# MINIOLED.net
KiCad netlist of a schematic drawn in Altium Designer
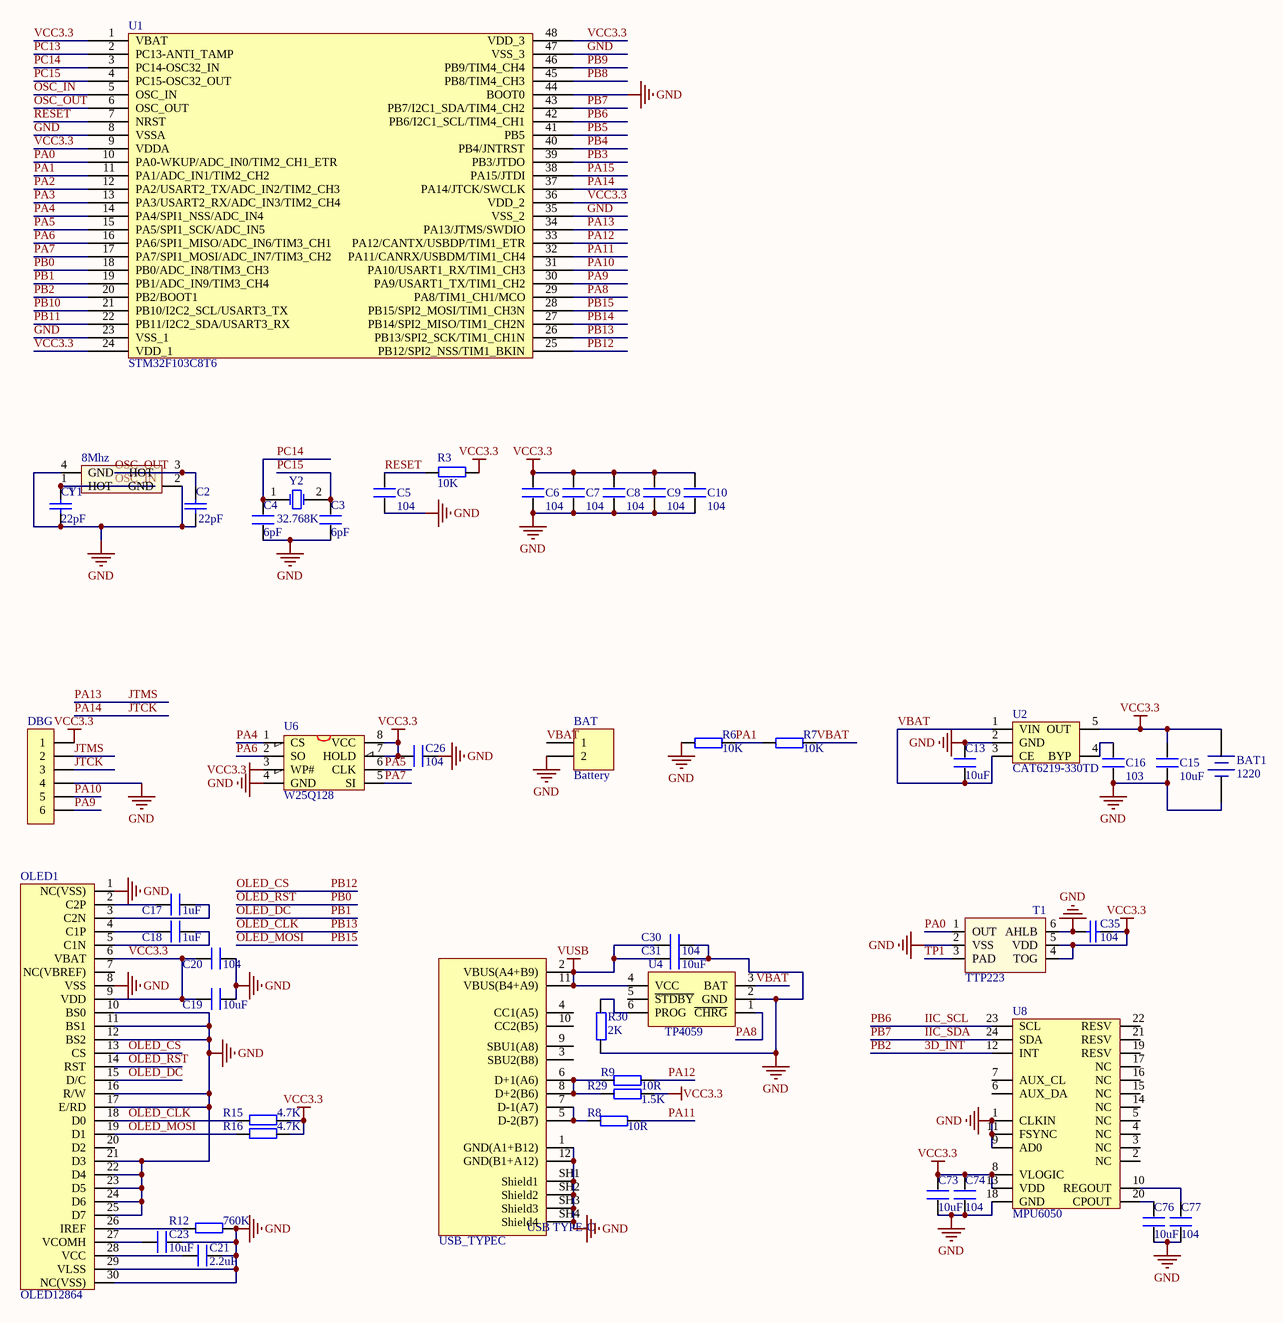
[diagram p0: MINIOLED.SchDoc]

(export (version "E")
  (design (tool "Eeschema 10.0.6"))
  (components
    (comp (ref "BAT")
      (value "Battery")
      (footprint "HDR1X2")
      (description "Header, 2-Pin")
      (fields (field (name "PUBLISHER") "Altium Limited"))
      (libsource (lib "MiniFly ") (part "Header 2"))
    )
    (comp (ref "BAT1")
      (value "1220")
      (footprint "CR1220_B")
      (description "微型电池")
      (fields (field (name "版权归属") "源创客"))
      (libsource (lib "IMX6UL_ALPHA(底板)_V2.0") (part "CR-3V"))
    )
    (comp (ref "C1") (value "22pF") (footprint "C 0402_L") (libsource (lib "L476") (part "CAP")))
    (comp (ref "C2") (value "22pF") (footprint "C 0402_L") (libsource (lib "L476") (part "CAP")))
    (comp (ref "C3")
      (value "6pF")
      (footprint "C 0402_L")
      (libsource (lib "WarShip V3 STM32103封装库") (part "C"))
    )
    (comp (ref "C4")
      (value "6pF")
      (footprint "C 0402_L")
      (libsource (lib "WarShip V3 STM32103封装库") (part "C"))
    )
    (comp (ref "C5")
      (value "104")
      (footprint "C 0402_L")
      (libsource (lib "WarShip V3 STM32103封装库") (part "C"))
    )
    (comp (ref "C6")
      (value "104")
      (footprint "C 0402_L")
      (libsource (lib "WarShip V3 STM32103封装库") (part "C"))
    )
    (comp (ref "C7")
      (value "104")
      (footprint "C 0402_L")
      (libsource (lib "WarShip V3 STM32103封装库") (part "C"))
    )
    (comp (ref "C8")
      (value "104")
      (footprint "C 0402_L")
      (libsource (lib "WarShip V3 STM32103封装库") (part "C"))
    )
    (comp (ref "C9")
      (value "104")
      (footprint "C 0402_L")
      (libsource (lib "WarShip V3 STM32103封装库") (part "C"))
    )
    (comp (ref "C10")
      (value "104")
      (footprint "C 0402_L")
      (libsource (lib "WarShip V3 STM32103封装库") (part "C"))
    )
    (comp (ref "C13")
      (value "10uF")
      (footprint "C 0402_L")
      (libsource (lib "WarShip V3 STM32103封装库") (part "C"))
    )
    (comp (ref "C15")
      (value "10uF")
      (footprint "C 0402_L")
      (libsource (lib "WarShip V3 STM32103封装库") (part "C"))
    )
    (comp (ref "C16")
      (value "103")
      (footprint "C 0402_L")
      (libsource (lib "WarShip V3 STM32103封装库") (part "C"))
    )
    (comp (ref "C17")
      (value "1uF")
      (footprint "C 0402_L")
      (libsource (lib "WarShip V3 STM32103封装库") (part "C"))
    )
    (comp (ref "C18")
      (value "1uF")
      (footprint "C 0402_L")
      (libsource (lib "WarShip V3 STM32103封装库") (part "C"))
    )
    (comp (ref "C19")
      (value "10uF")
      (footprint "C 0402_L")
      (libsource (lib "WarShip V3 STM32103封装库") (part "C"))
    )
    (comp (ref "C20")
      (value "104")
      (footprint "C 0402_L")
      (libsource (lib "WarShip V3 STM32103封装库") (part "C"))
    )
    (comp (ref "C21")
      (value "2.2uF")
      (footprint "C 0402_L")
      (libsource (lib "WarShip V3 STM32103封装库") (part "C"))
    )
    (comp (ref "C23")
      (value "10uF")
      (footprint "C 0402_L")
      (libsource (lib "WarShip V3 STM32103封装库") (part "C"))
    )
    (comp (ref "C26")
      (value "104")
      (footprint "C 0603_L")
      (libsource (lib "WarShip V3 STM32103封装库") (part "C"))
    )
    (comp (ref "C30")
      (value "104")
      (footprint "C 0402_L")
      (libsource (lib "WarShip V3 STM32103封装库") (part "C"))
    )
    (comp (ref "C31")
      (value "10uF")
      (footprint "C 0402_L")
      (libsource (lib "WarShip V3 STM32103封装库") (part "C"))
    )
    (comp (ref "C35")
      (value "104")
      (footprint "C 0402_L")
      (libsource (lib "Pandora_STM32L4_Board_V2.4") (part "C-0603-SMD"))
    )
    (comp (ref "C73") (value "10uF") (footprint "C 0402_L") (libsource (lib "MYCOMLIB") (part "C")))
    (comp (ref "C74") (value "104") (footprint "C 0402_L") (libsource (lib "MYCOMLIB") (part "C")))
    (comp (ref "C76") (value "10uF") (footprint "C 0402_L") (libsource (lib "MYCOMLIB") (part "C")))
    (comp (ref "C77") (value "104") (footprint "C 0402_L") (libsource (lib "MYCOMLIB") (part "C")))
    (comp (ref "DBG")
      (value "GPS&COMPASS")
      (footprint "SH1.0 S-W-6P")
      (description "6P接插件")
      (fields (field (name "版权归属") "源创客"))
      (libsource (lib "ATKF405 V1.1") (part "Header 6"))
    )
    (comp (ref "OLED1")
      (value "OLED12864")
      (footprint "OLED1.3")
      (libsource (lib "OLED模块封装库") (part "OLED12864"))
    )
    (comp (ref "R3")
      (value "10K")
      (footprint "R 0402_L")
      (libsource (lib "WarShip V3 STM32103封装库") (part "R"))
    )
    (comp (ref "R6")
      (value "10K")
      (footprint "R 0402_L")
      (libsource (lib "WarShip V3 STM32103封装库") (part "R"))
    )
    (comp (ref "R7")
      (value "10K")
      (footprint "R 0402_L")
      (libsource (lib "WarShip V3 STM32103封装库") (part "R"))
    )
    (comp (ref "R8")
      (value "10R")
      (footprint "R 0402_L")
      (libsource (lib "WarShip V3 STM32103封装库") (part "R"))
    )
    (comp (ref "R9")
      (value "10R")
      (footprint "R 0402_L")
      (libsource (lib "WarShip V3 STM32103封装库") (part "R"))
    )
    (comp (ref "R12")
      (value "760K")
      (footprint "R 0402_L")
      (libsource (lib "WarShip V3 STM32103封装库") (part "R"))
    )
    (comp (ref "R15")
      (value "4.7K")
      (footprint "R 0402_L")
      (libsource (lib "WarShip V3 STM32103封装库") (part "R"))
    )
    (comp (ref "R16")
      (value "4.7K")
      (footprint "R 0402_L")
      (libsource (lib "WarShip V3 STM32103封装库") (part "R"))
    )
    (comp (ref "R29")
      (value "1.5K")
      (footprint "R 0402_L")
      (libsource (lib "WarShip V3 STM32103封装库") (part "R"))
    )
    (comp (ref "R30")
      (value "2K")
      (footprint "R 0402_L")
      (libsource (lib "WarShip V3 STM32103封装库") (part "R"))
    )
    (comp (ref "T1")
      (value "TTP223")
      (footprint "SOT23-6L")
      (libsource (lib "nrf52832model") (part "TTP223"))
    )
    (comp (ref "U1")
      (value "STM32F103C8T6")
      (footprint "LQFP48 7X7_L")
      (libsource (lib "Pandora_STM32L4_Board_V2.4") (part "U-STM32F103C8T6"))
    )
    (comp (ref "U2")
      (value "CAT6219-330TD")
      (footprint "SOT-23-5")
      (description "3.3V 500mA LDO")
      (libsource (lib "STM32H743核心板封装库") (part "CAT6219-330TD"))
    )
    (comp (ref "U4")
      (value "TP4059")
      (footprint "SOT23-6L")
      (libsource (lib "ATK-2014-09-12") (part "TP4059"))
    )
    (comp (ref "U6")
      (value "W25Q128")
      (footprint "SOP8W_L")
      (description "W25X16;SST25VF016;MX25L1605")
      (libsource (lib "WarShip V3 STM32103封装库") (part "W25X16"))
    )
    (comp (ref "U8")
      (value "MPU6050")
      (footprint "QFN24 4x4_N")
      (description "9轴运动处理传感器")
      (libsource (lib "ALIENTEK_COMPONENT") (part "MPU6050"))
    )
    (comp (ref "USB_TYPEC")
      (value "USB TypeC")
      (footprint "USB Type-C")
      (description "12P TypeC 母座")
      (libsource (lib "ESP32_Weather") (part "USB Type-C"))
    )
    (comp (ref "Y1")
      (value "8Mhz")
      (footprint "XTAL-3225")
      (description "3225贴片无源晶振")
      (libsource (lib "ALIENTEK_COMPONENT") (part "XTAL_3225"))
    )
    (comp (ref "Y2")
      (value "32.768K")
      (footprint "OSC 3215-2P")
      (description "Crystal Oscillator")
      (fields (field (name "PUBLISHER") "Altium Limited"))
      (libsource (lib "WarShip V3 STM32103封装库") (part "XTAL"))
    )
  )
  (nets
    (net (code "1") (name "/3D_INT") (class "Default")
      (node (ref "U1") (pin "20") (pinfunction "PB2/BOOT1_20") (pintype "passive"))
      (node (ref "U8") (pin "12") (pinfunction "INT_12") (pintype "passive"))
    )
    (net (code "2") (name "/IIC_SCL") (class "Default")
      (node (ref "U1") (pin "42") (pinfunction "PB6/I2C1_SCL/TIM4_CH1_42") (pintype "passive"))
      (node (ref "U8") (pin "23") (pinfunction "SCL_23") (pintype "passive"))
    )
    (net (code "3") (name "/IIC_SDA") (class "Default")
      (node (ref "U1") (pin "43") (pinfunction "PB7/I2C1_SDA/TIM4_CH2_43") (pintype "passive"))
      (node (ref "U8") (pin "24") (pinfunction "SDA_24") (pintype "passive"))
    )
    (net (code "4") (name "/JTCK") (class "Default")
      (node (ref "DBG") (pin "3") (pinfunction "3_3") (pintype "passive"))
      (node (ref "U1") (pin "37") (pinfunction "PA14/JTCK/SWCLK_37") (pintype "passive"))
    )
    (net (code "5") (name "/JTMS") (class "Default")
      (node (ref "DBG") (pin "2") (pinfunction "2_2") (pintype "passive"))
      (node (ref "U1") (pin "34") (pinfunction "PA13/JTMS/SWDIO_34") (pintype "passive"))
    )
    (net (code "6") (name "/OLED_CLK") (class "Default")
      (node (ref "OLED1") (pin "18") (pinfunction "D0_18") (pintype "passive"))
      (node (ref "R15") (pin "2") (pintype "passive"))
      (node (ref "U1") (pin "26") (pinfunction "PB13/SPI2_SCK/TIM1_CH1N_26") (pintype "passive"))
    )
    (net (code "7") (name "/OLED_CS") (class "Default")
      (node (ref "OLED1") (pin "13") (pinfunction "CS_13") (pintype "passive"))
      (node (ref "U1") (pin "25") (pinfunction "PB12/SPI2_NSS/TIM1_BKIN_25") (pintype "passive"))
    )
    (net (code "8") (name "/OLED_DC") (class "Default")
      (node (ref "OLED1") (pin "15") (pinfunction "D/C_15") (pintype "passive"))
      (node (ref "U1") (pin "19") (pinfunction "PB1/ADC_IN9/TIM3_CH4_19") (pintype "passive"))
    )
    (net (code "9") (name "/OLED_MOSI") (class "Default")
      (node (ref "OLED1") (pin "19") (pinfunction "D1_19") (pintype "passive"))
      (node (ref "R16") (pin "2") (pintype "passive"))
      (node (ref "U1") (pin "28") (pinfunction "PB15/SPI2_MOSI/TIM1_CH3N_28") (pintype "passive"))
    )
    (net (code "10") (name "/OLED_RST") (class "Default")
      (node (ref "OLED1") (pin "14") (pinfunction "RST_14") (pintype "passive"))
      (node (ref "U1") (pin "18") (pinfunction "PB0/ADC_IN8/TIM3_CH3_18") (pintype "passive"))
    )
    (net (code "11") (name "/OSC_IN") (class "Default")
      (node (ref "C1") (pin "2") (pinfunction "2_2") (pintype "passive"))
      (node (ref "U1") (pin "5") (pinfunction "OSC_IN_5") (pintype "passive"))
      (node (ref "Y1") (pin "1") (pinfunction "HOT_1") (pintype "passive"))
    )
    (net (code "12") (name "/OSC_OUT") (class "Default")
      (node (ref "C2") (pin "2") (pinfunction "2_2") (pintype "passive"))
      (node (ref "U1") (pin "6") (pinfunction "OSC_OUT_6") (pintype "passive"))
      (node (ref "Y1") (pin "3") (pinfunction "HOT_3") (pintype "passive"))
    )
    (net (code "13") (name "/PA0") (class "Default")
      (node (ref "T1") (pin "1") (pinfunction "OUT_1") (pintype "passive"))
      (node (ref "U1") (pin "10") (pinfunction "PA0-WKUP/ADC_IN0/TIM2_CH1_ETR_10") (pintype "passive"))
    )
    (net (code "14") (name "/PA1") (class "Default")
      (node (ref "R6") (pin "2") (pintype "passive"))
      (node (ref "R7") (pin "1") (pintype "passive"))
      (node (ref "U1") (pin "11") (pinfunction "PA1/ADC_IN1/TIM2_CH2_11") (pintype "passive"))
    )
    (net (code "15") (name "/PA2") (class "Default")
      (node (ref "U1") (pin "12") (pinfunction "PA2/USART2_TX/ADC_IN2/TIM2_CH3_12") (pintype "passive"))
    )
    (net (code "16") (name "/PA3") (class "Default")
      (node (ref "U1") (pin "13") (pinfunction "PA3/USART2_RX/ADC_IN3/TIM2_CH4_13") (pintype "passive"))
    )
    (net (code "17") (name "/PA4") (class "Default")
      (node (ref "U1") (pin "14") (pinfunction "PA4/SPI1_NSS/ADC_IN4_14") (pintype "passive"))
      (node (ref "U6") (pin "1") (pinfunction "CS_1") (pintype "passive"))
    )
    (net (code "18") (name "/PA5") (class "Default")
      (node (ref "U1") (pin "15") (pinfunction "PA5/SPI1_SCK/ADC_IN5_15") (pintype "passive"))
      (node (ref "U6") (pin "6") (pinfunction "CLK_6") (pintype "passive"))
    )
    (net (code "19") (name "/PA6") (class "Default")
      (node (ref "U1") (pin "16") (pinfunction "PA6/SPI1_MISO/ADC_IN6/TIM3_CH1_16") (pintype "passive"))
      (node (ref "U6") (pin "2") (pinfunction "SO_2") (pintype "passive"))
    )
    (net (code "20") (name "/PA7") (class "Default")
      (node (ref "U1") (pin "17") (pinfunction "PA7/SPI1_MOSI/ADC_IN7/TIM3_CH2_17") (pintype "passive"))
      (node (ref "U6") (pin "5") (pinfunction "SI_5") (pintype "passive"))
    )
    (net (code "21") (name "/PA8") (class "Default")
      (node (ref "U1") (pin "29") (pinfunction "PA8/TIM1_CH1/MCO_29") (pintype "passive"))
      (node (ref "U4") (pin "1") (pinfunction "~{CHRG}_1") (pintype "passive"))
    )
    (net (code "22") (name "/PA9") (class "Default")
      (node (ref "DBG") (pin "6") (pinfunction "6_6") (pintype "passive"))
      (node (ref "U1") (pin "30") (pinfunction "PA9/USART1_TX/TIM1_CH2_30") (pintype "passive"))
    )
    (net (code "23") (name "/PA10") (class "Default")
      (node (ref "DBG") (pin "5") (pinfunction "5_5") (pintype "passive"))
      (node (ref "U1") (pin "31") (pinfunction "PA10/USART1_RX/TIM1_CH3_31") (pintype "passive"))
    )
    (net (code "24") (name "/PA11") (class "Default")
      (node (ref "R8") (pin "2") (pintype "passive"))
      (node (ref "U1") (pin "32") (pinfunction "PA11/CANRX/USBDM/TIM1_CH4_32") (pintype "passive"))
    )
    (net (code "25") (name "/PA12") (class "Default")
      (node (ref "R9") (pin "2") (pintype "passive"))
      (node (ref "U1") (pin "33") (pinfunction "PA12/CANTX/USBDP/TIM1_ETR_33") (pintype "passive"))
    )
    (net (code "26") (name "/PA15") (class "Default")
      (node (ref "U1") (pin "38") (pinfunction "PA15/JTDI_38") (pintype "passive"))
    )
    (net (code "27") (name "/PB3") (class "Default")
      (node (ref "U1") (pin "39") (pinfunction "PB3/JTDO_39") (pintype "passive"))
    )
    (net (code "28") (name "/PB4") (class "Default")
      (node (ref "U1") (pin "40") (pinfunction "PB4/JNTRST_40") (pintype "passive"))
    )
    (net (code "29") (name "/PB5") (class "Default")
      (node (ref "U1") (pin "41") (pinfunction "PB5_41") (pintype "passive"))
    )
    (net (code "30") (name "/PB8") (class "Default")
      (node (ref "U1") (pin "45") (pinfunction "PB8/TIM4_CH3_45") (pintype "passive"))
    )
    (net (code "31") (name "/PB9") (class "Default")
      (node (ref "U1") (pin "46") (pinfunction "PB9/TIM4_CH4_46") (pintype "passive"))
    )
    (net (code "32") (name "/PB10") (class "Default")
      (node (ref "U1") (pin "21") (pinfunction "PB10/I2C2_SCL/USART3_TX_21") (pintype "passive"))
    )
    (net (code "33") (name "/PB11") (class "Default")
      (node (ref "U1") (pin "22") (pinfunction "PB11/I2C2_SDA/USART3_RX_22") (pintype "passive"))
    )
    (net (code "34") (name "/PB14") (class "Default")
      (node (ref "U1") (pin "27") (pinfunction "PB14/SPI2_MISO/TIM1_CH2N_27") (pintype "passive"))
    )
    (net (code "35") (name "/PC13") (class "Default")
      (node (ref "U1") (pin "2") (pinfunction "PC13-ANTI_TAMP_2") (pintype "passive"))
    )
    (net (code "36") (name "/PC14") (class "Default")
      (node (ref "C4") (pin "2") (pintype "passive"))
      (node (ref "U1") (pin "3") (pinfunction "PC14-OSC32_IN_3") (pintype "passive"))
      (node (ref "Y2") (pin "1") (pinfunction "OSC1_1") (pintype "passive"))
    )
    (net (code "37") (name "/PC15") (class "Default")
      (node (ref "C3") (pin "2") (pintype "passive"))
      (node (ref "U1") (pin "4") (pinfunction "PC15-OSC32_OUT_4") (pintype "passive"))
      (node (ref "Y2") (pin "2") (pinfunction "OSC2_2") (pintype "passive"))
    )
    (net (code "38") (name "/RESET") (class "Default")
      (node (ref "C5") (pin "2") (pintype "passive"))
      (node (ref "R3") (pin "2") (pintype "passive"))
      (node (ref "U1") (pin "7") (pinfunction "NRST_7") (pintype "passive"))
    )
    (net (code "39") (name "/TP1") (class "Default")
      (node (ref "T1") (pin "3") (pinfunction "PAD_3") (pintype "passive"))
    )
    (net (code "40") (name "/VBAT") (class "Default")
      (node (ref "BAT") (pin "1") (pinfunction "1_1") (pintype "passive"))
      (node (ref "C13") (pin "1") (pintype "passive"))
      (node (ref "R7") (pin "2") (pintype "passive"))
      (node (ref "U2") (pin "1") (pinfunction "VIN_1") (pintype "passive"))
      (node (ref "U2") (pin "3") (pinfunction "CE_3") (pintype "passive"))
      (node (ref "U4") (pin "3") (pinfunction "BAT_3") (pintype "passive"))
    )
    (net (code "41") (name "GND") (class "Default")
      (node (ref "BAT") (pin "2") (pinfunction "2_2") (pintype "passive"))
      (node (ref "BAT1") (pin "2") (pinfunction "DC-_2") (pintype "passive"))
      (node (ref "C1") (pin "1") (pinfunction "1_1") (pintype "passive"))
      (node (ref "C10") (pin "1") (pintype "passive"))
      (node (ref "C13") (pin "2") (pintype "passive"))
      (node (ref "C15") (pin "1") (pintype "passive"))
      (node (ref "C16") (pin "1") (pintype "passive"))
      (node (ref "C19") (pin "1") (pintype "passive"))
      (node (ref "C2") (pin "1") (pinfunction "1_1") (pintype "passive"))
      (node (ref "C20") (pin "1") (pintype "passive"))
      (node (ref "C21") (pin "1") (pintype "passive"))
      (node (ref "C23") (pin "1") (pintype "passive"))
      (node (ref "C26") (pin "2") (pintype "passive"))
      (node (ref "C3") (pin "1") (pintype "passive"))
      (node (ref "C30") (pin "1") (pintype "passive"))
      (node (ref "C31") (pin "1") (pintype "passive"))
      (node (ref "C35") (pin "2") (pinfunction "2_2") (pintype "passive"))
      (node (ref "C4") (pin "1") (pintype "passive"))
      (node (ref "C5") (pin "1") (pintype "passive"))
      (node (ref "C6") (pin "1") (pintype "passive"))
      (node (ref "C7") (pin "1") (pintype "passive"))
      (node (ref "C73") (pin "2") (pintype "passive"))
      (node (ref "C74") (pin "1") (pintype "passive"))
      (node (ref "C76") (pin "1") (pintype "passive"))
      (node (ref "C77") (pin "2") (pintype "passive"))
      (node (ref "C8") (pin "1") (pintype "passive"))
      (node (ref "C9") (pin "1") (pintype "passive"))
      (node (ref "DBG") (pin "4") (pinfunction "4_4") (pintype "passive"))
      (node (ref "OLED1") (pin "1") (pinfunction "NC(VSS)_1") (pintype "passive"))
      (node (ref "OLED1") (pin "10") (pinfunction "BS0_10") (pintype "passive"))
      (node (ref "OLED1") (pin "11") (pinfunction "BS1_11") (pintype "passive"))
      (node (ref "OLED1") (pin "12") (pinfunction "BS2_12") (pintype "passive"))
      (node (ref "OLED1") (pin "16") (pinfunction "R/W_16") (pintype "passive"))
      (node (ref "OLED1") (pin "17") (pinfunction "E/RD_17") (pintype "passive"))
      (node (ref "OLED1") (pin "21") (pinfunction "D3_21") (pintype "passive"))
      (node (ref "OLED1") (pin "22") (pinfunction "D4_22") (pintype "passive"))
      (node (ref "OLED1") (pin "23") (pinfunction "D5_23") (pintype "passive"))
      (node (ref "OLED1") (pin "24") (pinfunction "D6_24") (pintype "passive"))
      (node (ref "OLED1") (pin "25") (pinfunction "D7_25") (pintype "passive"))
      (node (ref "OLED1") (pin "29") (pinfunction "VLSS_29") (pintype "passive"))
      (node (ref "OLED1") (pin "30") (pinfunction "NC(VSS)_30") (pintype "passive"))
      (node (ref "OLED1") (pin "8") (pinfunction "VSS_8") (pintype "passive"))
      (node (ref "R12") (pin "1") (pintype "passive"))
      (node (ref "R30") (pin "1") (pintype "passive"))
      (node (ref "R6") (pin "1") (pintype "passive"))
      (node (ref "T1") (pin "2") (pinfunction "VSS_2") (pintype "passive"))
      (node (ref "T1") (pin "6") (pinfunction "AHLB_6") (pintype "passive"))
      (node (ref "U1") (pin "23") (pinfunction "VSS_1_23") (pintype "passive"))
      (node (ref "U1") (pin "35") (pinfunction "VSS_2_35") (pintype "passive"))
      (node (ref "U1") (pin "44") (pinfunction "BOOT0_44") (pintype "passive"))
      (node (ref "U1") (pin "47") (pinfunction "VSS_3_47") (pintype "passive"))
      (node (ref "U1") (pin "8") (pinfunction "VSSA_8") (pintype "passive"))
      (node (ref "U2") (pin "2") (pinfunction "GND_2") (pintype "passive"))
      (node (ref "U4") (pin "2") (pinfunction "GND_2") (pintype "passive"))
      (node (ref "U6") (pin "4") (pinfunction "GND_4") (pintype "passive"))
      (node (ref "U8") (pin "1") (pinfunction "CLKIN_1") (pintype "passive"))
      (node (ref "U8") (pin "11") (pinfunction "FSYNC_11") (pintype "passive"))
      (node (ref "U8") (pin "18") (pinfunction "GND_18") (pintype "passive"))
      (node (ref "U8") (pin "9") (pinfunction "AD0_9") (pintype "passive"))
      (node (ref "USB_TYPEC") (pin "1") (pinfunction "GND(A1+B12)_1") (pintype "passive"))
      (node (ref "USB_TYPEC") (pin "12") (pinfunction "GND(B1+A12)_12") (pintype "passive"))
      (node (ref "USB_TYPEC") (pin "SH1") (pinfunction "Shield1_SH1") (pintype "passive"))
      (node (ref "USB_TYPEC") (pin "SH2") (pinfunction "Shield2_SH2") (pintype "passive"))
      (node (ref "USB_TYPEC") (pin "SH3") (pinfunction "Shield3_SH3") (pintype "passive"))
      (node (ref "USB_TYPEC") (pin "SH4") (pinfunction "Shield4_SH4") (pintype "passive"))
      (node (ref "Y1") (pin "2") (pinfunction "GND_2") (pintype "passive"))
      (node (ref "Y1") (pin "4") (pinfunction "GND_4") (pintype "passive"))
    )
    (net (code "42") (name "Net-(OLED1-C1N)") (class "Default")
      (node (ref "C18") (pin "1") (pintype "passive"))
      (node (ref "OLED1") (pin "5") (pinfunction "C1N_5") (pintype "passive"))
    )
    (net (code "43") (name "Net-(OLED1-C1P)") (class "Default")
      (node (ref "C18") (pin "2") (pintype "passive"))
      (node (ref "OLED1") (pin "4") (pinfunction "C1P_4") (pintype "passive"))
    )
    (net (code "44") (name "Net-(OLED1-C2N)") (class "Default")
      (node (ref "C17") (pin "1") (pintype "passive"))
      (node (ref "OLED1") (pin "3") (pinfunction "C2N_3") (pintype "passive"))
    )
    (net (code "45") (name "Net-(OLED1-C2P)") (class "Default")
      (node (ref "C17") (pin "2") (pintype "passive"))
      (node (ref "OLED1") (pin "2") (pinfunction "C2P_2") (pintype "passive"))
    )
    (net (code "46") (name "Net-(OLED1-IREF)") (class "Default")
      (node (ref "OLED1") (pin "26") (pinfunction "IREF_26") (pintype "passive"))
      (node (ref "R12") (pin "2") (pintype "passive"))
    )
    (net (code "47") (name "Net-(OLED1-VCC)") (class "Default")
      (node (ref "C21") (pin "2") (pintype "passive"))
      (node (ref "OLED1") (pin "28") (pinfunction "VCC_28") (pintype "passive"))
    )
    (net (code "48") (name "Net-(OLED1-VCOMH)") (class "Default")
      (node (ref "C23") (pin "2") (pintype "passive"))
      (node (ref "OLED1") (pin "27") (pinfunction "VCOMH_27") (pintype "passive"))
    )
    (net (code "49") (name "Net-(U2-BYP)") (class "Default")
      (node (ref "C16") (pin "2") (pintype "passive"))
      (node (ref "U2") (pin "4") (pinfunction "BYP_4") (pintype "passive"))
    )
    (net (code "50") (name "Net-(U4-PROG)") (class "Default")
      (node (ref "R30") (pin "2") (pintype "passive"))
      (node (ref "U4") (pin "6") (pinfunction "PROG_6") (pintype "passive"))
    )
    (net (code "51") (name "Net-(U8-CPOUT)") (class "Default")
      (node (ref "C76") (pin "2") (pintype "passive"))
      (node (ref "U8") (pin "20") (pinfunction "CPOUT_20") (pintype "passive"))
    )
    (net (code "52") (name "Net-(U8-REGOUT)") (class "Default")
      (node (ref "C77") (pin "1") (pintype "passive"))
      (node (ref "U8") (pin "10") (pinfunction "REGOUT_10") (pintype "passive"))
    )
    (net (code "53") (name "Net-(USB_TYPEC-D+1(A6))") (class "Default")
      (node (ref "R29") (pin "1") (pintype "passive"))
      (node (ref "R9") (pin "1") (pintype "passive"))
      (node (ref "USB_TYPEC") (pin "6") (pinfunction "D+1(A6)_6") (pintype "passive"))
      (node (ref "USB_TYPEC") (pin "8") (pinfunction "D+2(B6)_8") (pintype "passive"))
    )
    (net (code "54") (name "Net-(USB_TYPEC-D-1(A7))") (class "Default")
      (node (ref "R8") (pin "1") (pintype "passive"))
      (node (ref "USB_TYPEC") (pin "5") (pinfunction "D-2(B7)_5") (pintype "passive"))
      (node (ref "USB_TYPEC") (pin "7") (pinfunction "D-1(A7)_7") (pintype "passive"))
    )
    (net (code "55") (name "VCC3.3") (class "Default")
      (node (ref "BAT1") (pin "1") (pinfunction "DC+_1") (pintype "passive"))
      (node (ref "C10") (pin "2") (pintype "passive"))
      (node (ref "C15") (pin "2") (pintype "passive"))
      (node (ref "C19") (pin "2") (pintype "passive"))
      (node (ref "C20") (pin "2") (pintype "passive"))
      (node (ref "C26") (pin "1") (pintype "passive"))
      (node (ref "C35") (pin "1") (pinfunction "1_1") (pintype "passive"))
      (node (ref "C6") (pin "2") (pintype "passive"))
      (node (ref "C7") (pin "2") (pintype "passive"))
      (node (ref "C73") (pin "1") (pintype "passive"))
      (node (ref "C74") (pin "2") (pintype "passive"))
      (node (ref "C8") (pin "2") (pintype "passive"))
      (node (ref "C9") (pin "2") (pintype "passive"))
      (node (ref "DBG") (pin "1") (pinfunction "1_1") (pintype "passive"))
      (node (ref "OLED1") (pin "6") (pinfunction "VBAT_6") (pintype "passive"))
      (node (ref "OLED1") (pin "9") (pinfunction "VDD_9") (pintype "passive"))
      (node (ref "R15") (pin "1") (pintype "passive"))
      (node (ref "R16") (pin "1") (pintype "passive"))
      (node (ref "R29") (pin "2") (pintype "passive"))
      (node (ref "R3") (pin "1") (pintype "passive"))
      (node (ref "T1") (pin "4") (pinfunction "TOG_4") (pintype "passive"))
      (node (ref "T1") (pin "5") (pinfunction "VDD_5") (pintype "passive"))
      (node (ref "U1") (pin "1") (pinfunction "VBAT_1") (pintype "passive"))
      (node (ref "U1") (pin "24") (pinfunction "VDD_1_24") (pintype "passive"))
      (node (ref "U1") (pin "36") (pinfunction "VDD_2_36") (pintype "passive"))
      (node (ref "U1") (pin "48") (pinfunction "VDD_3_48") (pintype "passive"))
      (node (ref "U1") (pin "9") (pinfunction "VDDA_9") (pintype "passive"))
      (node (ref "U2") (pin "5") (pinfunction "OUT_5") (pintype "passive"))
      (node (ref "U6") (pin "3") (pinfunction "WP#_3") (pintype "passive"))
      (node (ref "U6") (pin "7") (pinfunction "HOLD_7") (pintype "passive"))
      (node (ref "U6") (pin "8") (pinfunction "VCC_8") (pintype "passive"))
      (node (ref "U8") (pin "13") (pinfunction "VDD_13") (pintype "passive"))
      (node (ref "U8") (pin "8") (pinfunction "VLOGIC_8") (pintype "passive"))
    )
    (net (code "56") (name "VUSB") (class "Default")
      (node (ref "C30") (pin "2") (pintype "passive"))
      (node (ref "C31") (pin "2") (pintype "passive"))
      (node (ref "U4") (pin "4") (pinfunction "VCC_4") (pintype "passive"))
      (node (ref "USB_TYPEC") (pin "11") (pinfunction "VBUS(B4+A9)_11") (pintype "passive"))
      (node (ref "USB_TYPEC") (pin "2") (pinfunction "VBUS(A4+B9)_2") (pintype "passive"))
    )
    (net (code "57") (name "unconnected-(OLED1-D2-Pad20)") (class "Default")
      (node (ref "OLED1") (pin "20") (pinfunction "D2_20") (pintype "passive"))
    )
    (net (code "58") (name "unconnected-(OLED1-NC(VBREF)-Pad7)") (class "Default")
      (node (ref "OLED1") (pin "7") (pinfunction "NC(VBREF)_7") (pintype "passive"))
    )
    (net (code "59") (name "unconnected-(U4-~{STDBY}-Pad5)") (class "Default")
      (node (ref "U4") (pin "5") (pinfunction "~{STDBY}_5") (pintype "passive"))
    )
    (net (code "60") (name "unconnected-(U8-AUX_CL-Pad7)") (class "Default")
      (node (ref "U8") (pin "7") (pinfunction "AUX_CL_7") (pintype "passive"))
    )
    (net (code "61") (name "unconnected-(U8-AUX_DA-Pad6)") (class "Default")
      (node (ref "U8") (pin "6") (pinfunction "AUX_DA_6") (pintype "passive"))
    )
    (net (code "62") (name "unconnected-(U8-NC-Pad2)") (class "Default")
      (node (ref "U8") (pin "2") (pinfunction "NC_2") (pintype "passive"))
    )
    (net (code "63") (name "unconnected-(U8-NC-Pad3)") (class "Default")
      (node (ref "U8") (pin "3") (pinfunction "NC_3") (pintype "passive"))
    )
    (net (code "64") (name "unconnected-(U8-NC-Pad4)") (class "Default")
      (node (ref "U8") (pin "4") (pinfunction "NC_4") (pintype "passive"))
    )
    (net (code "65") (name "unconnected-(U8-NC-Pad5)") (class "Default")
      (node (ref "U8") (pin "5") (pinfunction "NC_5") (pintype "passive"))
    )
    (net (code "66") (name "unconnected-(U8-NC-Pad14)") (class "Default")
      (node (ref "U8") (pin "14") (pinfunction "NC_14") (pintype "passive"))
    )
    (net (code "67") (name "unconnected-(U8-NC-Pad15)") (class "Default")
      (node (ref "U8") (pin "15") (pinfunction "NC_15") (pintype "passive"))
    )
    (net (code "68") (name "unconnected-(U8-NC-Pad16)") (class "Default")
      (node (ref "U8") (pin "16") (pinfunction "NC_16") (pintype "passive"))
    )
    (net (code "69") (name "unconnected-(U8-NC-Pad17)") (class "Default")
      (node (ref "U8") (pin "17") (pinfunction "NC_17") (pintype "passive"))
    )
    (net (code "70") (name "unconnected-(U8-RESV-Pad19)") (class "Default")
      (node (ref "U8") (pin "19") (pinfunction "RESV_19") (pintype "passive"))
    )
    (net (code "71") (name "unconnected-(U8-RESV-Pad21)") (class "Default")
      (node (ref "U8") (pin "21") (pinfunction "RESV_21") (pintype "passive"))
    )
    (net (code "72") (name "unconnected-(U8-RESV-Pad22)") (class "Default")
      (node (ref "U8") (pin "22") (pinfunction "RESV_22") (pintype "passive"))
    )
    (net (code "73") (name "unconnected-(USB_TYPEC-CC1(A5)-Pad4)") (class "Default")
      (node (ref "USB_TYPEC") (pin "4") (pinfunction "CC1(A5)_4") (pintype "passive"))
    )
    (net (code "74") (name "unconnected-(USB_TYPEC-CC2(B5)-Pad10)") (class "Default")
      (node (ref "USB_TYPEC") (pin "10") (pinfunction "CC2(B5)_10") (pintype "passive"))
    )
    (net (code "75") (name "unconnected-(USB_TYPEC-SBU1(A8)-Pad9)") (class "Default")
      (node (ref "USB_TYPEC") (pin "9") (pinfunction "SBU1(A8)_9") (pintype "passive"))
    )
    (net (code "76") (name "unconnected-(USB_TYPEC-SBU2(B8)-Pad3)") (class "Default")
      (node (ref "USB_TYPEC") (pin "3") (pinfunction "SBU2(B8)_3") (pintype "passive"))
    )
  )
)
